# mcu.net
KiCad netlist of a schematic drawn in Altium Designer
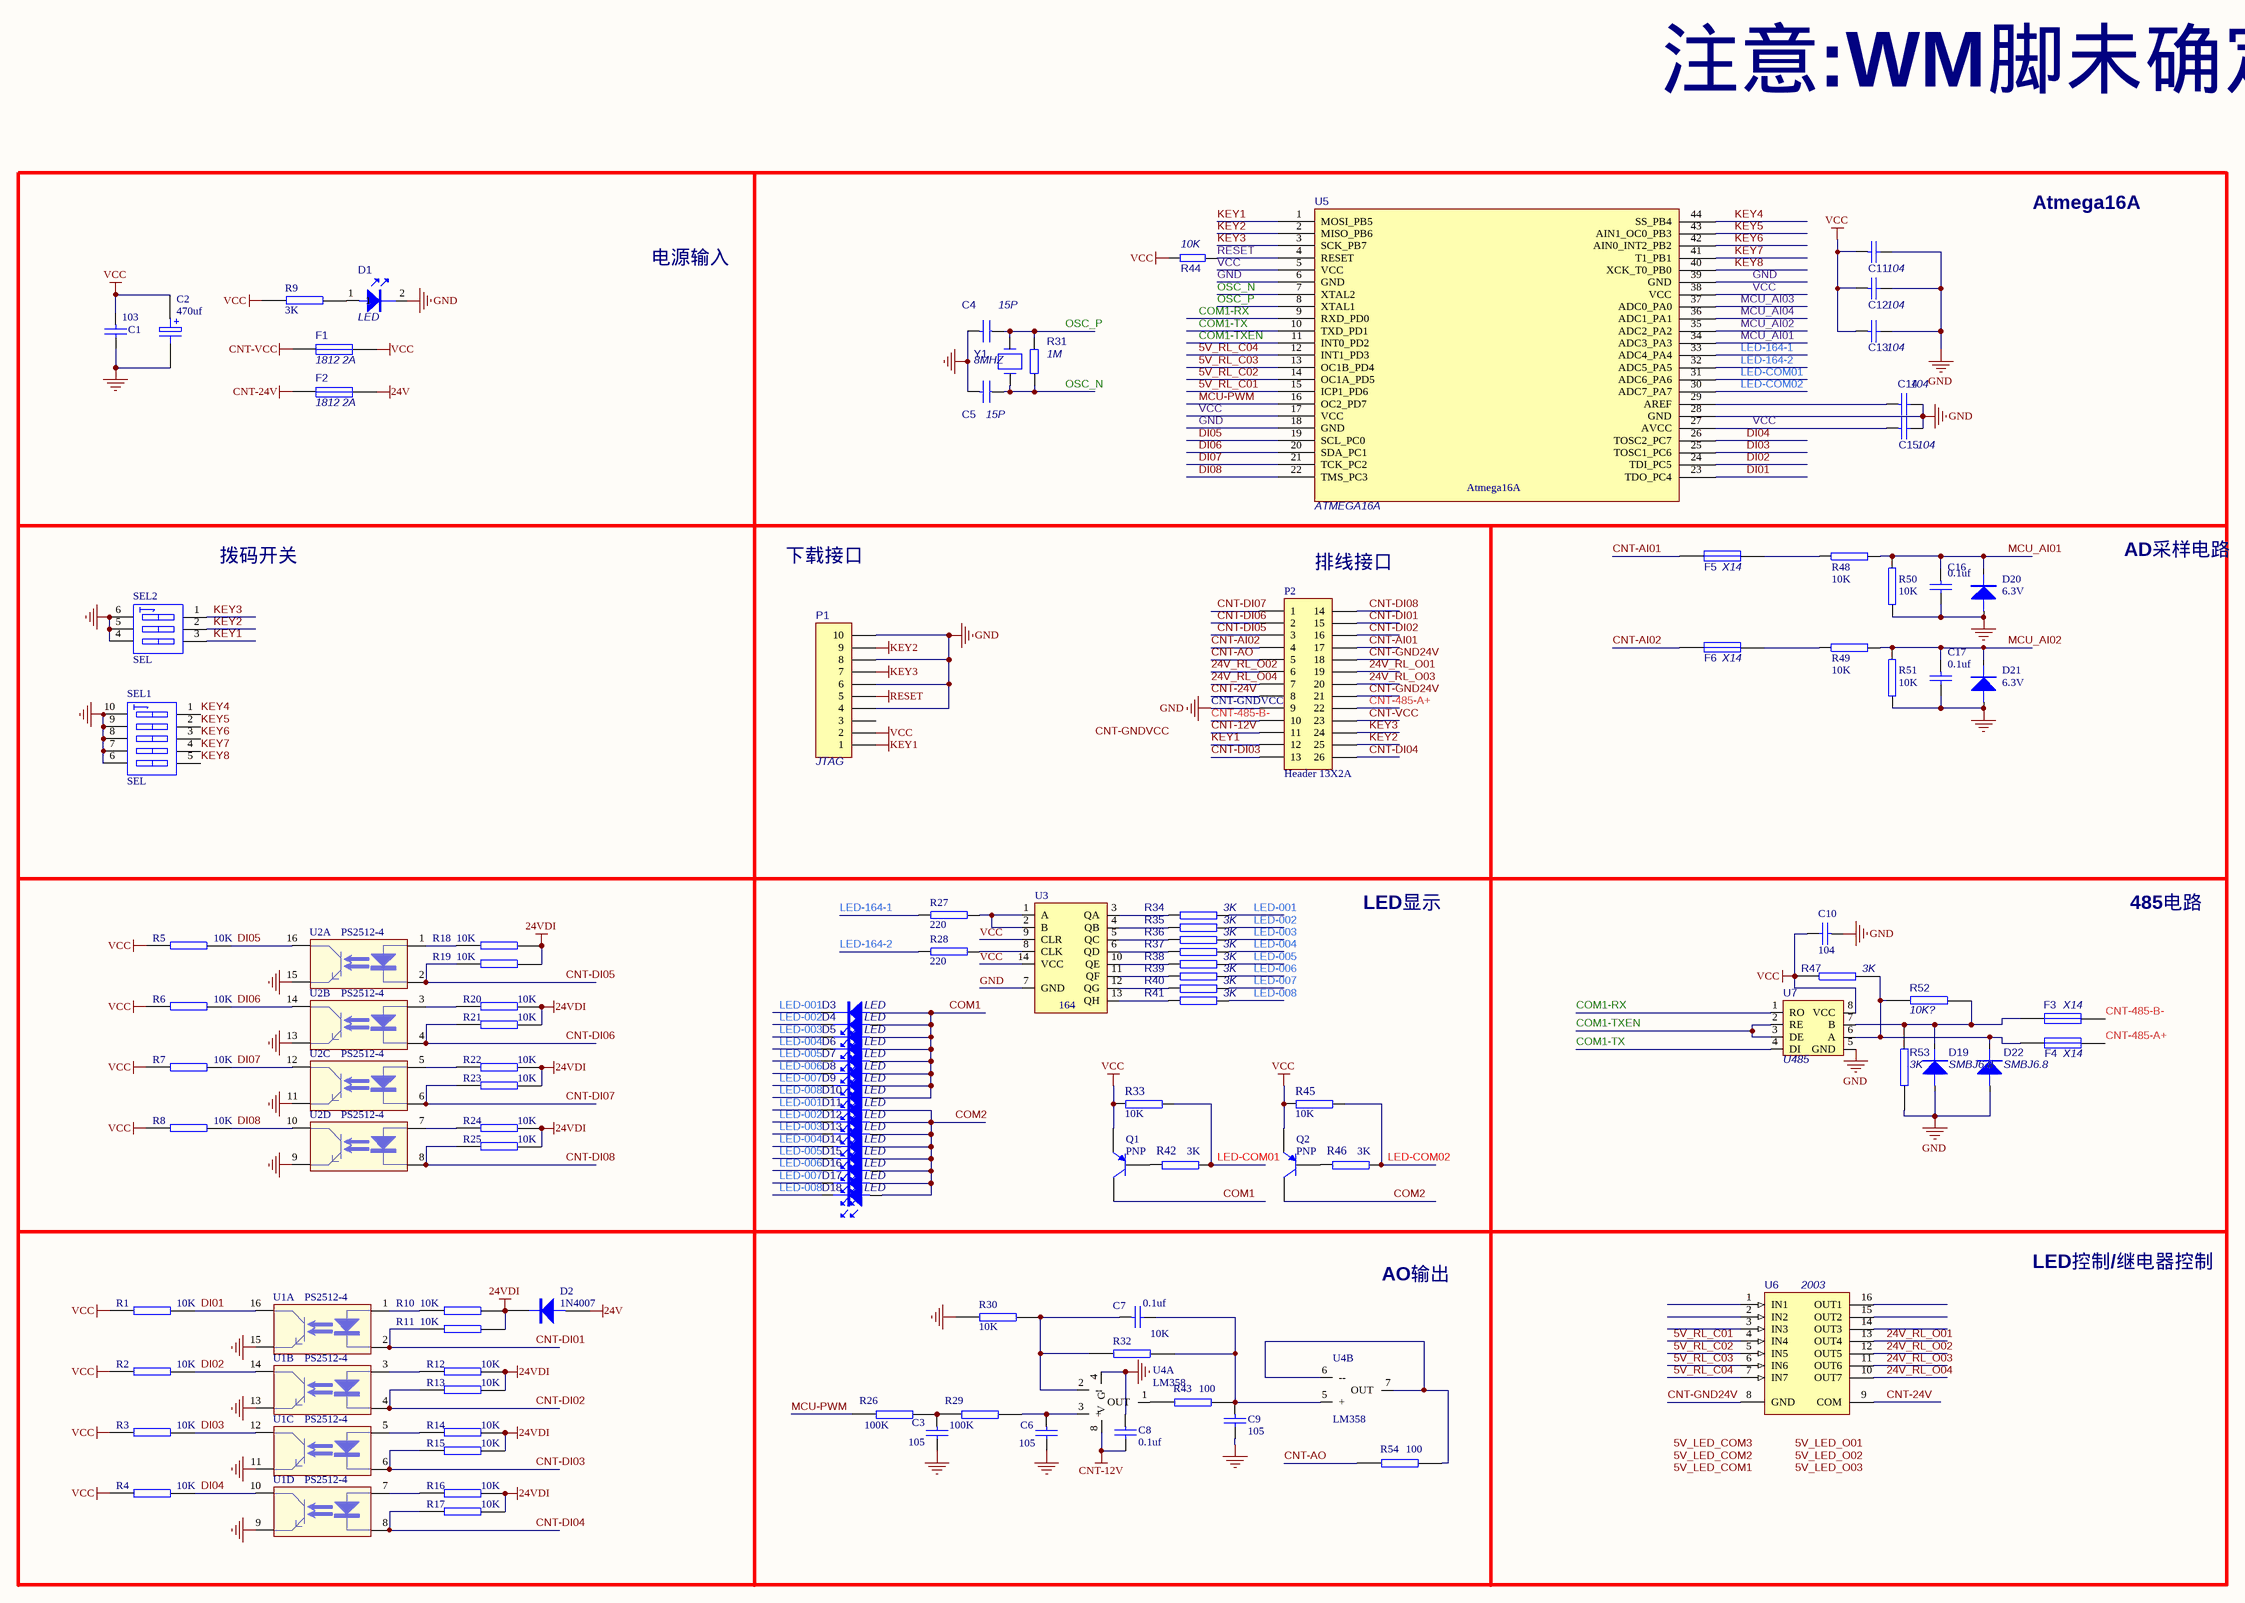
[diagram p0: mcu.SchDoc]

(export (version "E")
  (design (tool "Eeschema 10.0.6"))
  (components
    (comp (ref "C1")
      (value "103")
      (footprint "C0805")
      (description "Capacitor")
      (libsource (lib "*") (part "CAP"))
    )
    (comp (ref "C2")
      (value "470uf")
      (footprint "E8MM")
      (description "Electrolytic Capacitor")
      (libsource (lib "*") (part "ELECTRO1"))
    )
    (comp (ref "C3")
      (value "105")
      (footprint "c0805")
      (description "Capacitor")
      (libsource (lib "*") (part "CAP"))
    )
    (comp (ref "C4") (value "15P") (footprint "C0805") (libsource (lib "*") (part "CAP NP")))
    (comp (ref "C5") (value "15P") (footprint "C0805") (libsource (lib "*") (part "CAP NP")))
    (comp (ref "C6")
      (value "105")
      (footprint "c0805")
      (description "Capacitor")
      (libsource (lib "*") (part "CAP"))
    )
    (comp (ref "C7")
      (value "0.1uf")
      (footprint "C0805")
      (description "Capacitor")
      (libsource (lib "*") (part "CAP"))
    )
    (comp (ref "C8")
      (value "0.1uf")
      (footprint "C0805")
      (description "Capacitor")
      (libsource (lib "*") (part "CAP"))
    )
    (comp (ref "C9")
      (value "105")
      (footprint "c0805")
      (description "Capacitor")
      (libsource (lib "*") (part "CAP"))
    )
    (comp (ref "C10")
      (value "104")
      (footprint "C0805")
      (description "Capacitor")
      (libsource (lib "*") (part "CAP"))
    )
    (comp (ref "C11")
      (value "104")
      (footprint "C0805")
      (description "Capacitor")
      (libsource (lib "*") (part "CAP"))
    )
    (comp (ref "C12")
      (value "104")
      (footprint "C0805")
      (description "Capacitor")
      (libsource (lib "*") (part "CAP"))
    )
    (comp (ref "C13")
      (value "104")
      (footprint "C0805")
      (description "Capacitor")
      (libsource (lib "*") (part "CAP"))
    )
    (comp (ref "C14")
      (value "104")
      (footprint "C0805")
      (description "Capacitor")
      (libsource (lib "*") (part "CAP"))
    )
    (comp (ref "C15")
      (value "104")
      (footprint "C0805")
      (description "Capacitor")
      (libsource (lib "*") (part "CAP"))
    )
    (comp (ref "C16")
      (value "0.1uf")
      (footprint "C0805")
      (description "Capacitor")
      (libsource (lib "*") (part "CAP"))
    )
    (comp (ref "C17")
      (value "0.1uf")
      (footprint "C0805")
      (description "Capacitor")
      (libsource (lib "*") (part "CAP"))
    )
    (comp (ref "D1") (value "LED") (footprint "LED0805") (libsource (lib "*") (part "LED")))
    (comp (ref "D2")
      (value "1N4007")
      (footprint "M7")
      (description "Diode")
      (libsource (lib "") (part "DIODE_1"))
    )
    (comp (ref "D3") (value "LED") (footprint "LED0805") (libsource (lib "") (part "LED_1")))
    (comp (ref "D4") (value "LED") (footprint "LED0805") (libsource (lib "") (part "LED_1")))
    (comp (ref "D5") (value "LED") (footprint "LED0805") (libsource (lib "") (part "LED_1")))
    (comp (ref "D6") (value "LED") (footprint "LED0805") (libsource (lib "") (part "LED_1")))
    (comp (ref "D7") (value "LED") (footprint "LED0805") (libsource (lib "") (part "LED_1")))
    (comp (ref "D8") (value "LED") (footprint "LED0805") (libsource (lib "") (part "LED_1")))
    (comp (ref "D9") (value "LED") (footprint "LED0805") (libsource (lib "") (part "LED_1")))
    (comp (ref "D10") (value "LED") (footprint "LED0805") (libsource (lib "") (part "LED_1")))
    (comp (ref "D11") (value "LED") (footprint "LED0805") (libsource (lib "") (part "LED_1")))
    (comp (ref "D12") (value "LED") (footprint "LED0805") (libsource (lib "") (part "LED_1")))
    (comp (ref "D13") (value "LED") (footprint "LED0805") (libsource (lib "") (part "LED_1")))
    (comp (ref "D14") (value "LED") (footprint "LED0805") (libsource (lib "") (part "LED_1")))
    (comp (ref "D15") (value "LED") (footprint "LED0805") (libsource (lib "") (part "LED_1")))
    (comp (ref "D16") (value "LED") (footprint "LED0805") (libsource (lib "") (part "LED_1")))
    (comp (ref "D17") (value "LED") (footprint "LED0805") (libsource (lib "") (part "LED_1")))
    (comp (ref "D18") (value "LED") (footprint "LED0805") (libsource (lib "") (part "LED_1")))
    (comp (ref "D19")
      (value "SMBJ6.8")
      (footprint "SMBJ_SMT")
      (description "Diode")
      (libsource (lib "*") (part "DIODE"))
    )
    (comp (ref "D20")
      (value "6.3V")
      (footprint "1206AK")
      (description "Diode")
      (libsource (lib "*") (part "DIODE"))
    )
    (comp (ref "D21")
      (value "6.3V")
      (footprint "1206AK")
      (description "Diode")
      (libsource (lib "*") (part "DIODE"))
    )
    (comp (ref "D22")
      (value "SMBJ6.8")
      (footprint "SMBJ_SMT")
      (description "Diode")
      (libsource (lib "*") (part "DIODE"))
    )
    (comp (ref "F1")
      (value "1812 2A")
      (footprint "F1210")
      (description "Fuse")
      (fields (field (name "PUBLISHER") "Altium Limited"))
      (libsource (lib "Miscellaneous Devices") (part "Fuse 1"))
    )
    (comp (ref "F2")
      (value "1812 2A")
      (footprint "F1210")
      (description "Fuse")
      (fields (field (name "PUBLISHER") "Altium Limited"))
      (libsource (lib "Miscellaneous Devices") (part "Fuse 1"))
    )
    (comp (ref "F3")
      (value "X14")
      (footprint "F1210")
      (description "Fuse")
      (fields (field (name "PUBLISHER") "Altium Limited"))
      (libsource (lib "Miscellaneous Devices") (part "Fuse 1"))
    )
    (comp (ref "F4")
      (value "X14")
      (footprint "F1210")
      (description "Fuse")
      (fields (field (name "PUBLISHER") "Altium Limited"))
      (libsource (lib "Miscellaneous Devices") (part "Fuse 1"))
    )
    (comp (ref "F5")
      (value "X14")
      (footprint "F1210")
      (description "Fuse")
      (fields (field (name "PUBLISHER") "Altium Limited"))
      (libsource (lib "Miscellaneous Devices") (part "Fuse 1"))
    )
    (comp (ref "F6")
      (value "X14")
      (footprint "F1210")
      (description "Fuse")
      (fields (field (name "PUBLISHER") "Altium Limited"))
      (libsource (lib "Miscellaneous Devices") (part "Fuse 1"))
    )
    (comp (ref "P1")
      (value "JTAG")
      (footprint "FC10")
      (description "Connector")
      (libsource (lib "*") (part "CON10"))
    )
    (comp (ref "P2")
      (value "Header 13X2A")
      (footprint "HDR2X13_CEN")
      (description "Header, 13-Pin, Dual row")
      (fields (field (name "PUBLISHER") "Altium Limited"))
      (libsource (lib "Miscellaneous Connectors") (part "Header 13X2A"))
    )
    (comp (ref "Q1")
      (value "PNP")
      (footprint "SOT23")
      (description "PNP Bipolar Transistor")
      (fields (field (name "PUBLISHER") "Altium Limited"))
      (libsource (lib "Miscellaneous Devices") (part "PNP"))
    )
    (comp (ref "Q2")
      (value "PNP")
      (footprint "SOT23")
      (description "PNP Bipolar Transistor")
      (fields (field (name "PUBLISHER") "Altium Limited"))
      (libsource (lib "Miscellaneous Devices") (part "PNP"))
    )
    (comp (ref "R1") (value "10K") (footprint "0805R") (libsource (lib "*") (part "RES2")))
    (comp (ref "R2") (value "10K") (footprint "0805R") (libsource (lib "*") (part "RES2")))
    (comp (ref "R3") (value "10K") (footprint "0805R") (libsource (lib "*") (part "RES2")))
    (comp (ref "R4") (value "10K") (footprint "0805R") (libsource (lib "*") (part "RES2")))
    (comp (ref "R5") (value "10K") (footprint "0805R") (libsource (lib "*") (part "RES2")))
    (comp (ref "R6") (value "10K") (footprint "0805R") (libsource (lib "*") (part "RES2")))
    (comp (ref "R7") (value "10K") (footprint "0805R") (libsource (lib "*") (part "RES2")))
    (comp (ref "R8") (value "10K") (footprint "0805R") (libsource (lib "*") (part "RES2")))
    (comp (ref "R9") (value "3K") (footprint "0805R") (libsource (lib "*") (part "RES2")))
    (comp (ref "R10") (value "10K") (footprint "0805R") (libsource (lib "*") (part "RES2")))
    (comp (ref "R11") (value "10K") (footprint "0805R") (libsource (lib "*") (part "RES2")))
    (comp (ref "R12") (value "10K") (footprint "0805R") (libsource (lib "*") (part "RES2")))
    (comp (ref "R13") (value "10K") (footprint "0805R") (libsource (lib "*") (part "RES2")))
    (comp (ref "R14") (value "10K") (footprint "0805R") (libsource (lib "*") (part "RES2")))
    (comp (ref "R15") (value "10K") (footprint "0805R") (libsource (lib "*") (part "RES2")))
    (comp (ref "R16") (value "10K") (footprint "0805R") (libsource (lib "*") (part "RES2")))
    (comp (ref "R17") (value "10K") (footprint "0805R") (libsource (lib "*") (part "RES2")))
    (comp (ref "R18") (value "10K") (footprint "0805R") (libsource (lib "*") (part "RES2")))
    (comp (ref "R19") (value "10K") (footprint "0805R") (libsource (lib "*") (part "RES2")))
    (comp (ref "R20") (value "10K") (footprint "0805R") (libsource (lib "*") (part "RES2")))
    (comp (ref "R21") (value "10K") (footprint "0805R") (libsource (lib "*") (part "RES2")))
    (comp (ref "R22") (value "10K") (footprint "0805R") (libsource (lib "*") (part "RES2")))
    (comp (ref "R23") (value "10K") (footprint "0805R") (libsource (lib "*") (part "RES2")))
    (comp (ref "R24") (value "10K") (footprint "0805R") (libsource (lib "*") (part "RES2")))
    (comp (ref "R25") (value "10K") (footprint "0805R") (libsource (lib "*") (part "RES2")))
    (comp (ref "R26") (value "100K") (footprint "0805R") (libsource (lib "*") (part "RES2")))
    (comp (ref "R27") (value "220") (footprint "0805R") (libsource (lib "") (part "RES2_3")))
    (comp (ref "R28") (value "220") (footprint "0805R") (libsource (lib "") (part "RES2_3")))
    (comp (ref "R29") (value "100K") (footprint "0805R") (libsource (lib "*") (part "RES2")))
    (comp (ref "R30") (value "10K") (footprint "0805R") (libsource (lib "*") (part "RES2")))
    (comp (ref "R31") (value "1M") (footprint "0805R") (libsource (lib "*") (part "res")))
    (comp (ref "R32") (value "10K") (footprint "0805R") (libsource (lib "*") (part "RES2")))
    (comp (ref "R33") (value "10K") (footprint "0805R") (libsource (lib "") (part "RES2_2")))
    (comp (ref "R34") (value "3K") (footprint "0805R") (libsource (lib "") (part "RES2_1")))
    (comp (ref "R35") (value "3K") (footprint "0805R") (libsource (lib "") (part "RES2_1")))
    (comp (ref "R36") (value "3K") (footprint "0805R") (libsource (lib "") (part "RES2_1")))
    (comp (ref "R37") (value "3K") (footprint "0805R") (libsource (lib "") (part "RES2_1")))
    (comp (ref "R38") (value "3K") (footprint "0805R") (libsource (lib "") (part "RES2_1")))
    (comp (ref "R39") (value "3K") (footprint "0805R") (libsource (lib "") (part "RES2_1")))
    (comp (ref "R40") (value "3K") (footprint "0805R") (libsource (lib "") (part "RES2_1")))
    (comp (ref "R41") (value "3K") (footprint "0805R") (libsource (lib "") (part "RES2_1")))
    (comp (ref "R42") (value "3K") (footprint "0805R") (libsource (lib "") (part "RES2_2")))
    (comp (ref "R43") (value "100") (footprint "0805R") (libsource (lib "*") (part "RES2")))
    (comp (ref "R44") (value "10K") (footprint "0805R") (libsource (lib "*") (part "res")))
    (comp (ref "R45") (value "10K") (footprint "0805R") (libsource (lib "") (part "RES2_2")))
    (comp (ref "R46") (value "3K") (footprint "0805R") (libsource (lib "") (part "RES2_2")))
    (comp (ref "R47") (value "3K") (footprint "0805R") (libsource (lib "*") (part "RES2")))
    (comp (ref "R48") (value "10K") (footprint "0805R") (libsource (lib "") (part "RES2_1")))
    (comp (ref "R49") (value "10K") (footprint "0805R") (libsource (lib "") (part "RES2_1")))
    (comp (ref "R50") (value "10K") (footprint "0805R") (libsource (lib "") (part "RES2_1")))
    (comp (ref "R51") (value "10K") (footprint "0805R") (libsource (lib "") (part "RES2_1")))
    (comp (ref "R52") (value "10K?") (footprint "0805R") (libsource (lib "*") (part "RES2")))
    (comp (ref "R53") (value "3K") (footprint "0805R") (libsource (lib "*") (part "RES2")))
    (comp (ref "R54") (value "100") (footprint "0805R") (libsource (lib "*") (part "RES2")))
    (comp (ref "SEL1")
      (value "SEL")
      (footprint "N10A")
      (description "DIP Switch, 5 Position, SPST")
      (fields (field (name "PUBLISHER") "Altium Limited"))
      (libsource (lib "Miscellaneous Devices") (part "SW DIP-5"))
    )
    (comp (ref "SEL2")
      (value "SEL")
      (footprint "DIP-6")
      (description "DIP Switch, 3 Position, SPST")
      (fields (field (name "PUBLISHER") "Altium Limited"))
      (libsource (lib "Miscellaneous Devices") (part "SW DIP-3"))
    )
    (comp (ref "U1") (value "PS2512-4") (footprint "SO_16") (libsource (lib "Atkey_2") (part "PS2512-4")))
    (comp (ref "U2") (value "PS2512-4") (footprint "SO_16") (libsource (lib "Atkey_2") (part "PS2512-4")))
    (comp (ref "U3") (value "164") (footprint "SO_14") (libsource (lib "*") (part "164")))
    (comp (ref "U4") (value "LM358") (footprint "SO_08") (libsource (lib "*") (part "LM358")))
    (comp (ref "U5") (value "ATMEGA16A") (footprint "qfp44") (libsource (lib "CL-FFU") (part "ATMEGA16A")))
    (comp (ref "U6")
      (value "2003")
      (footprint "SO_16")
      (description "High-Voltage, High-Current Darlington Array")
      (fields (field (name "PUBLISHER") "*"))
      (libsource (lib "*") (part "ULN2003A"))
    )
    (comp (ref "U7") (value "U485") (footprint "SOP8") (libsource (lib "POL485") (part "U485")))
    (comp (ref "Y1") (value "8MHZ") (footprint "XAL2") (libsource (lib "*") (part "CRYSTAL")))
  )
  (nets
    (net (code "7") (name "/5V_RL_C01") (class "Default")
      (node (ref "U5") (pin "15") (pinfunction "ICP1_PD6_15") (pintype "passive"))
      (node (ref "U6") (pin "4") (pinfunction "IN4_4") (pintype "input"))
    )
    (net (code "8") (name "/5V_RL_C02") (class "Default")
      (node (ref "U5") (pin "14") (pinfunction "OC1A_PD5_14") (pintype "passive"))
      (node (ref "U6") (pin "5") (pinfunction "IN5_5") (pintype "input"))
    )
    (net (code "9") (name "/5V_RL_C03") (class "Default")
      (node (ref "U5") (pin "13") (pinfunction "OC1B_PD4_13") (pintype "passive"))
      (node (ref "U6") (pin "6") (pinfunction "IN6_6") (pintype "input"))
    )
    (net (code "10") (name "/5V_RL_C04") (class "Default")
      (node (ref "U5") (pin "12") (pinfunction "INT1_PD3_12") (pintype "passive"))
      (node (ref "U6") (pin "7") (pinfunction "IN7_7") (pintype "input"))
    )
    (net (code "11") (name "/24V_RL_O01") (class "Default")
      (node (ref "P2") (pin "19") (pinfunction "19_19") (pintype "passive"))
      (node (ref "U6") (pin "13") (pinfunction "OUT4_13") (pintype "open_collector"))
    )
    (net (code "12") (name "/24V_RL_O02") (class "Default")
      (node (ref "P2") (pin "6") (pinfunction "6_6") (pintype "passive"))
      (node (ref "U6") (pin "12") (pinfunction "OUT5_12") (pintype "open_collector"))
    )
    (net (code "13") (name "/24V_RL_O03") (class "Default")
      (node (ref "P2") (pin "20") (pinfunction "20_20") (pintype "passive"))
      (node (ref "U6") (pin "11") (pinfunction "OUT6_11") (pintype "open_collector"))
    )
    (net (code "14") (name "/24V_RL_O04") (class "Default")
      (node (ref "P2") (pin "7") (pinfunction "7_7") (pintype "passive"))
      (node (ref "U6") (pin "10") (pinfunction "OUT7_10") (pintype "open_collector"))
    )
    (net (code "15") (name "/CNT-485-A+") (class "Default")
      (node (ref "F4") (pin "1") (pinfunction "1_1") (pintype "passive"))
      (node (ref "P2") (pin "22") (pinfunction "22_22") (pintype "passive"))
    )
    (net (code "16") (name "/CNT-485-B-") (class "Default")
      (node (ref "F3") (pin "1") (pinfunction "1_1") (pintype "passive"))
      (node (ref "P2") (pin "10") (pinfunction "10_10") (pintype "passive"))
    )
    (net (code "17") (name "/CNT-AI01") (class "Default")
      (node (ref "F5") (pin "2") (pinfunction "2_2") (pintype "passive"))
      (node (ref "P2") (pin "17") (pinfunction "17_17") (pintype "passive"))
    )
    (net (code "18") (name "/CNT-AI02") (class "Default")
      (node (ref "F6") (pin "2") (pinfunction "2_2") (pintype "passive"))
      (node (ref "P2") (pin "4") (pinfunction "4_4") (pintype "passive"))
    )
    (net (code "19") (name "/CNT-AO") (class "Default")
      (node (ref "P2") (pin "5") (pinfunction "5_5") (pintype "passive"))
      (node (ref "R54") (pin "1") (pinfunction "1_1") (pintype "passive"))
    )
    (net (code "20") (name "/CNT-DI01") (class "Default")
      (node (ref "P2") (pin "15") (pinfunction "15_15") (pintype "passive"))
      (node (ref "R11") (pin "2") (pinfunction "2_2") (pintype "passive"))
      (node (ref "U1") (pin "2") (pinfunction "2_2") (pintype "passive"))
    )
    (net (code "21") (name "/CNT-DI02") (class "Default")
      (node (ref "P2") (pin "16") (pinfunction "16_16") (pintype "passive"))
      (node (ref "R13") (pin "2") (pinfunction "2_2") (pintype "passive"))
      (node (ref "U1") (pin "4") (pinfunction "4_4") (pintype "passive"))
    )
    (net (code "22") (name "/CNT-DI03") (class "Default")
      (node (ref "P2") (pin "13") (pinfunction "13_13") (pintype "passive"))
      (node (ref "R15") (pin "2") (pinfunction "2_2") (pintype "passive"))
      (node (ref "U1") (pin "6") (pinfunction "6_6") (pintype "passive"))
    )
    (net (code "23") (name "/CNT-DI04") (class "Default")
      (node (ref "P2") (pin "26") (pinfunction "26_26") (pintype "passive"))
      (node (ref "R17") (pin "2") (pinfunction "2_2") (pintype "passive"))
      (node (ref "U1") (pin "8") (pinfunction "8_8") (pintype "passive"))
    )
    (net (code "24") (name "/CNT-DI05") (class "Default")
      (node (ref "P2") (pin "3") (pinfunction "3_3") (pintype "passive"))
      (node (ref "R19") (pin "2") (pinfunction "2_2") (pintype "passive"))
      (node (ref "U2") (pin "2") (pinfunction "2_2") (pintype "passive"))
    )
    (net (code "25") (name "/CNT-DI06") (class "Default")
      (node (ref "P2") (pin "2") (pinfunction "2_2") (pintype "passive"))
      (node (ref "R21") (pin "2") (pinfunction "2_2") (pintype "passive"))
      (node (ref "U2") (pin "4") (pinfunction "4_4") (pintype "passive"))
    )
    (net (code "26") (name "/CNT-DI07") (class "Default")
      (node (ref "P2") (pin "1") (pinfunction "1_1") (pintype "passive"))
      (node (ref "R23") (pin "2") (pinfunction "2_2") (pintype "passive"))
      (node (ref "U2") (pin "6") (pinfunction "6_6") (pintype "passive"))
    )
    (net (code "27") (name "/CNT-DI08") (class "Default")
      (node (ref "P2") (pin "14") (pinfunction "14_14") (pintype "passive"))
      (node (ref "R25") (pin "2") (pinfunction "2_2") (pintype "passive"))
      (node (ref "U2") (pin "8") (pinfunction "8_8") (pintype "passive"))
    )
    (net (code "28") (name "/CNT-GND24V") (class "Default")
      (node (ref "P2") (pin "18") (pinfunction "18_18") (pintype "passive"))
      (node (ref "P2") (pin "21") (pinfunction "21_21") (pintype "passive"))
      (node (ref "U6") (pin "8") (pinfunction "GND_8") (pintype "power_in"))
    )
    (net (code "30") (name "/COM1") (class "Default")
      (node (ref "D10") (pin "1") (pinfunction "1_1") (pintype "passive"))
      (node (ref "D3") (pin "1") (pinfunction "1_1") (pintype "passive"))
      (node (ref "D4") (pin "1") (pinfunction "1_1") (pintype "passive"))
      (node (ref "D5") (pin "1") (pinfunction "1_1") (pintype "passive"))
      (node (ref "D6") (pin "1") (pinfunction "1_1") (pintype "passive"))
      (node (ref "D7") (pin "1") (pinfunction "1_1") (pintype "passive"))
      (node (ref "D8") (pin "1") (pinfunction "1_1") (pintype "passive"))
      (node (ref "D9") (pin "1") (pinfunction "1_1") (pintype "passive"))
      (node (ref "Q1") (pin "1") (pinfunction "C_1") (pintype "passive"))
    )
    (net (code "31") (name "/COM1-RX") (class "Default")
      (node (ref "U5") (pin "9") (pinfunction "RXD_PD0_9") (pintype "passive"))
      (node (ref "U7") (pin "1") (pinfunction "RO_1") (pintype "passive"))
    )
    (net (code "32") (name "/COM1-TX") (class "Default")
      (node (ref "U5") (pin "10") (pinfunction "TXD_PD1_10") (pintype "passive"))
      (node (ref "U7") (pin "4") (pinfunction "DI_4") (pintype "passive"))
    )
    (net (code "33") (name "/COM1-TXEN") (class "Default")
      (node (ref "U5") (pin "11") (pinfunction "INT0_PD2_11") (pintype "passive"))
      (node (ref "U7") (pin "2") (pinfunction "RE_2") (pintype "passive"))
      (node (ref "U7") (pin "3") (pinfunction "DE_3") (pintype "passive"))
    )
    (net (code "34") (name "/COM2") (class "Default")
      (node (ref "D11") (pin "1") (pinfunction "1_1") (pintype "passive"))
      (node (ref "D12") (pin "1") (pinfunction "1_1") (pintype "passive"))
      (node (ref "D13") (pin "1") (pinfunction "1_1") (pintype "passive"))
      (node (ref "D14") (pin "1") (pinfunction "1_1") (pintype "passive"))
      (node (ref "D15") (pin "1") (pinfunction "1_1") (pintype "passive"))
      (node (ref "D16") (pin "1") (pinfunction "1_1") (pintype "passive"))
      (node (ref "D17") (pin "1") (pinfunction "1_1") (pintype "passive"))
      (node (ref "D18") (pin "1") (pinfunction "1_1") (pintype "passive"))
      (node (ref "Q2") (pin "1") (pinfunction "C_1") (pintype "passive"))
    )
    (net (code "35") (name "/DI01") (class "Default")
      (node (ref "R1") (pin "1") (pinfunction "1_1") (pintype "passive"))
      (node (ref "U1") (pin "16") (pinfunction "16_16") (pintype "passive"))
      (node (ref "U5") (pin "23") (pinfunction "TDO_PC4_23") (pintype "passive"))
    )
    (net (code "36") (name "/DI02") (class "Default")
      (node (ref "R2") (pin "1") (pinfunction "1_1") (pintype "passive"))
      (node (ref "U1") (pin "14") (pinfunction "14_14") (pintype "passive"))
      (node (ref "U5") (pin "24") (pinfunction "TDI_PC5_24") (pintype "passive"))
    )
    (net (code "37") (name "/DI03") (class "Default")
      (node (ref "R3") (pin "1") (pinfunction "1_1") (pintype "passive"))
      (node (ref "U1") (pin "12") (pinfunction "12_12") (pintype "passive"))
      (node (ref "U5") (pin "25") (pinfunction "TOSC1_PC6_25") (pintype "passive"))
    )
    (net (code "38") (name "/DI04") (class "Default")
      (node (ref "R4") (pin "1") (pinfunction "1_1") (pintype "passive"))
      (node (ref "U1") (pin "10") (pinfunction "10_10") (pintype "passive"))
      (node (ref "U5") (pin "26") (pinfunction "TOSC2_PC7_26") (pintype "passive"))
    )
    (net (code "39") (name "/DI05") (class "Default")
      (node (ref "R5") (pin "1") (pinfunction "1_1") (pintype "passive"))
      (node (ref "U2") (pin "16") (pinfunction "16_16") (pintype "passive"))
      (node (ref "U5") (pin "19") (pinfunction "SCL_PC0_19") (pintype "passive"))
    )
    (net (code "40") (name "/DI06") (class "Default")
      (node (ref "R6") (pin "1") (pinfunction "1_1") (pintype "passive"))
      (node (ref "U2") (pin "14") (pinfunction "14_14") (pintype "passive"))
      (node (ref "U5") (pin "20") (pinfunction "SDA_PC1_20") (pintype "passive"))
    )
    (net (code "41") (name "/DI07") (class "Default")
      (node (ref "R7") (pin "1") (pinfunction "1_1") (pintype "passive"))
      (node (ref "U2") (pin "12") (pinfunction "12_12") (pintype "passive"))
      (node (ref "U5") (pin "21") (pinfunction "TCK_PC2_21") (pintype "passive"))
    )
    (net (code "42") (name "/DI08") (class "Default")
      (node (ref "R8") (pin "1") (pinfunction "1_1") (pintype "passive"))
      (node (ref "U2") (pin "10") (pinfunction "10_10") (pintype "passive"))
      (node (ref "U5") (pin "22") (pinfunction "TMS_PC3_22") (pintype "passive"))
    )
    (net (code "43") (name "/KEY4") (class "Default")
      (node (ref "SEL1") (pin "1") (pinfunction "A1_1") (pintype "passive"))
      (node (ref "U5") (pin "44") (pinfunction "SS_PB4_44") (pintype "passive"))
    )
    (net (code "44") (name "/KEY5") (class "Default")
      (node (ref "SEL1") (pin "2") (pinfunction "A2_2") (pintype "passive"))
      (node (ref "U5") (pin "43") (pinfunction "AIN1_OC0_PB3_43") (pintype "passive"))
    )
    (net (code "45") (name "/KEY6") (class "Default")
      (node (ref "SEL1") (pin "3") (pinfunction "A3_3") (pintype "passive"))
      (node (ref "U5") (pin "42") (pinfunction "AIN0_INT2_PB2_42") (pintype "passive"))
    )
    (net (code "46") (name "/KEY7") (class "Default")
      (node (ref "SEL1") (pin "4") (pinfunction "A4_4") (pintype "passive"))
      (node (ref "U5") (pin "41") (pinfunction "T1_PB1_41") (pintype "passive"))
    )
    (net (code "47") (name "/KEY8") (class "Default")
      (node (ref "SEL1") (pin "5") (pinfunction "A5_5") (pintype "passive"))
      (node (ref "U5") (pin "40") (pinfunction "XCK_T0_PB0_40") (pintype "passive"))
    )
    (net (code "48") (name "/LED-001") (class "Default")
      (node (ref "D11") (pin "2") (pinfunction "2_2") (pintype "passive"))
      (node (ref "D3") (pin "2") (pinfunction "2_2") (pintype "passive"))
      (node (ref "R34") (pin "2") (pinfunction "2_2") (pintype "passive"))
    )
    (net (code "49") (name "/LED-002") (class "Default")
      (node (ref "D12") (pin "2") (pinfunction "2_2") (pintype "passive"))
      (node (ref "D4") (pin "2") (pinfunction "2_2") (pintype "passive"))
      (node (ref "R35") (pin "2") (pinfunction "2_2") (pintype "passive"))
    )
    (net (code "50") (name "/LED-003") (class "Default")
      (node (ref "D13") (pin "2") (pinfunction "2_2") (pintype "passive"))
      (node (ref "D5") (pin "2") (pinfunction "2_2") (pintype "passive"))
      (node (ref "R36") (pin "2") (pinfunction "2_2") (pintype "passive"))
    )
    (net (code "51") (name "/LED-004") (class "Default")
      (node (ref "D14") (pin "2") (pinfunction "2_2") (pintype "passive"))
      (node (ref "D6") (pin "2") (pinfunction "2_2") (pintype "passive"))
      (node (ref "R37") (pin "2") (pinfunction "2_2") (pintype "passive"))
    )
    (net (code "52") (name "/LED-005") (class "Default")
      (node (ref "D15") (pin "2") (pinfunction "2_2") (pintype "passive"))
      (node (ref "D7") (pin "2") (pinfunction "2_2") (pintype "passive"))
      (node (ref "R38") (pin "2") (pinfunction "2_2") (pintype "passive"))
    )
    (net (code "53") (name "/LED-006") (class "Default")
      (node (ref "D16") (pin "2") (pinfunction "2_2") (pintype "passive"))
      (node (ref "D8") (pin "2") (pinfunction "2_2") (pintype "passive"))
      (node (ref "R39") (pin "2") (pinfunction "2_2") (pintype "passive"))
    )
    (net (code "54") (name "/LED-007") (class "Default")
      (node (ref "D17") (pin "2") (pinfunction "2_2") (pintype "passive"))
      (node (ref "D9") (pin "2") (pinfunction "2_2") (pintype "passive"))
      (node (ref "R40") (pin "2") (pinfunction "2_2") (pintype "passive"))
    )
    (net (code "55") (name "/LED-008") (class "Default")
      (node (ref "D10") (pin "2") (pinfunction "2_2") (pintype "passive"))
      (node (ref "D18") (pin "2") (pinfunction "2_2") (pintype "passive"))
      (node (ref "R41") (pin "2") (pinfunction "2_2") (pintype "passive"))
    )
    (net (code "56") (name "/LED-164-1") (class "Default")
      (node (ref "R27") (pin "2") (pinfunction "2_2") (pintype "passive"))
      (node (ref "U5") (pin "33") (pinfunction "ADC4_PA4_33") (pintype "passive"))
    )
    (net (code "57") (name "/LED-164-2") (class "Default")
      (node (ref "R28") (pin "2") (pinfunction "2_2") (pintype "passive"))
      (node (ref "U5") (pin "32") (pinfunction "ADC5_PA5_32") (pintype "passive"))
    )
    (net (code "58") (name "/LED-COM01") (class "Default")
      (node (ref "R33") (pin "2") (pintype "passive"))
      (node (ref "R42") (pin "2") (pintype "passive"))
      (node (ref "U5") (pin "31") (pinfunction "ADC6_PA6_31") (pintype "passive"))
    )
    (net (code "59") (name "/LED-COM02") (class "Default")
      (node (ref "R45") (pin "2") (pintype "passive"))
      (node (ref "R46") (pin "2") (pintype "passive"))
      (node (ref "U5") (pin "30") (pinfunction "ADC7_PA7_30") (pintype "passive"))
    )
    (net (code "60") (name "/MCU-PWM") (class "Default")
      (node (ref "R26") (pin "1") (pinfunction "1_1") (pintype "passive"))
      (node (ref "U5") (pin "16") (pinfunction "OC2_PD7_16") (pintype "passive"))
    )
    (net (code "61") (name "/MCU_AI01") (class "Default")
      (node (ref "C16") (pin "1") (pinfunction "1_1") (pintype "passive"))
      (node (ref "D20") (pin "K") (pinfunction "K_K") (pintype "passive"))
      (node (ref "R48") (pin "2") (pinfunction "2_2") (pintype "passive"))
      (node (ref "R50") (pin "2") (pinfunction "2_2") (pintype "passive"))
      (node (ref "U5") (pin "34") (pinfunction "ADC3_PA3_34") (pintype "passive"))
    )
    (net (code "62") (name "/MCU_AI02") (class "Default")
      (node (ref "C17") (pin "1") (pinfunction "1_1") (pintype "passive"))
      (node (ref "D21") (pin "K") (pinfunction "K_K") (pintype "passive"))
      (node (ref "R49") (pin "2") (pinfunction "2_2") (pintype "passive"))
      (node (ref "R51") (pin "2") (pinfunction "2_2") (pintype "passive"))
      (node (ref "U5") (pin "35") (pinfunction "ADC2_PA2_35") (pintype "passive"))
    )
    (net (code "63") (name "/MCU_AI03") (class "Default")
      (node (ref "U5") (pin "37") (pinfunction "ADC0_PA0_37") (pintype "passive"))
    )
    (net (code "64") (name "/MCU_AI04") (class "Default")
      (node (ref "U5") (pin "36") (pinfunction "ADC1_PA1_36") (pintype "passive"))
    )
    (net (code "65") (name "/OSC_N") (class "Default")
      (node (ref "C5") (pin "1") (pinfunction "1_1") (pintype "passive"))
      (node (ref "R31") (pin "1") (pinfunction "1_1") (pintype "passive"))
      (node (ref "U5") (pin "7") (pinfunction "XTAL2_7") (pintype "passive"))
      (node (ref "Y1") (pin "2") (pinfunction "2_2") (pintype "passive"))
    )
    (net (code "66") (name "/OSC_P") (class "Default")
      (node (ref "C4") (pin "1") (pinfunction "1_1") (pintype "passive"))
      (node (ref "R31") (pin "2") (pinfunction "0_2") (pintype "passive"))
      (node (ref "U5") (pin "8") (pinfunction "XTAL1_8") (pintype "passive"))
      (node (ref "Y1") (pin "1") (pinfunction "1_1") (pintype "passive"))
    )
    (net (code "67") (name "24V") (class "Default")
      (node (ref "D2") (pin "1") (pinfunction "A_1") (pintype "passive"))
      (node (ref "F2") (pin "2") (pinfunction "2_2") (pintype "passive"))
    )
    (net (code "68") (name "24VDI") (class "Default")
      (node (ref "D2") (pin "2") (pinfunction "K_2") (pintype "passive"))
      (node (ref "R10") (pin "1") (pinfunction "1_1") (pintype "passive"))
      (node (ref "R11") (pin "1") (pinfunction "1_1") (pintype "passive"))
      (node (ref "R12") (pin "1") (pinfunction "1_1") (pintype "passive"))
      (node (ref "R13") (pin "1") (pinfunction "1_1") (pintype "passive"))
      (node (ref "R14") (pin "1") (pinfunction "1_1") (pintype "passive"))
      (node (ref "R15") (pin "1") (pinfunction "1_1") (pintype "passive"))
      (node (ref "R16") (pin "1") (pinfunction "1_1") (pintype "passive"))
      (node (ref "R17") (pin "1") (pinfunction "1_1") (pintype "passive"))
      (node (ref "R18") (pin "1") (pinfunction "1_1") (pintype "passive"))
      (node (ref "R19") (pin "1") (pinfunction "1_1") (pintype "passive"))
      (node (ref "R20") (pin "1") (pinfunction "1_1") (pintype "passive"))
      (node (ref "R21") (pin "1") (pinfunction "1_1") (pintype "passive"))
      (node (ref "R22") (pin "1") (pinfunction "1_1") (pintype "passive"))
      (node (ref "R23") (pin "1") (pinfunction "1_1") (pintype "passive"))
      (node (ref "R24") (pin "1") (pinfunction "1_1") (pintype "passive"))
      (node (ref "R25") (pin "1") (pinfunction "1_1") (pintype "passive"))
    )
    (net (code "69") (name "CNT-12V") (class "Default")
      (node (ref "C8") (pin "2") (pinfunction "2_2") (pintype "passive"))
      (node (ref "P2") (pin "11") (pinfunction "11_11") (pintype "passive"))
      (node (ref "U4") (pin "8") (pinfunction "V_8") (pintype "passive"))
    )
    (net (code "70") (name "CNT-24V") (class "Default")
      (node (ref "F2") (pin "1") (pinfunction "1_1") (pintype "passive"))
      (node (ref "P2") (pin "8") (pinfunction "8_8") (pintype "passive"))
      (node (ref "U6") (pin "9") (pinfunction "COM_9") (pintype "passive"))
    )
    (net (code "71") (name "CNT-VCC") (class "Default")
      (node (ref "F1") (pin "1") (pinfunction "1_1") (pintype "passive"))
      (node (ref "P2") (pin "23") (pinfunction "23_23") (pintype "passive"))
    )
    (net (code "72") (name "GND") (class "Default")
      (node (ref "C1") (pin "2") (pinfunction "2_2") (pintype "passive"))
      (node (ref "C10") (pin "1") (pinfunction "1_1") (pintype "passive"))
      (node (ref "C11") (pin "2") (pinfunction "2_2") (pintype "passive"))
      (node (ref "C12") (pin "2") (pinfunction "2_2") (pintype "passive"))
      (node (ref "C13") (pin "2") (pinfunction "2_2") (pintype "passive"))
      (node (ref "C14") (pin "2") (pinfunction "2_2") (pintype "passive"))
      (node (ref "C15") (pin "2") (pinfunction "2_2") (pintype "passive"))
      (node (ref "C16") (pin "2") (pinfunction "2_2") (pintype "passive"))
      (node (ref "C17") (pin "2") (pinfunction "2_2") (pintype "passive"))
      (node (ref "C2") (pin "2") (pinfunction "2_2") (pintype "passive"))
      (node (ref "C3") (pin "2") (pinfunction "2_2") (pintype "passive"))
      (node (ref "C4") (pin "2") (pinfunction "2_2") (pintype "passive"))
      (node (ref "C5") (pin "2") (pinfunction "2_2") (pintype "passive"))
      (node (ref "C6") (pin "2") (pinfunction "2_2") (pintype "passive"))
      (node (ref "C8") (pin "1") (pinfunction "1_1") (pintype "passive"))
      (node (ref "C9") (pin "2") (pinfunction "2_2") (pintype "passive"))
      (node (ref "D1") (pin "2") (pinfunction "2_2") (pintype "passive"))
      (node (ref "D19") (pin "A") (pinfunction "A_A") (pintype "passive"))
      (node (ref "D20") (pin "A") (pinfunction "A_A") (pintype "passive"))
      (node (ref "D21") (pin "A") (pinfunction "A_A") (pintype "passive"))
      (node (ref "D22") (pin "A") (pinfunction "A_A") (pintype "passive"))
      (node (ref "P1") (pin "10") (pinfunction "10_10") (pintype "passive"))
      (node (ref "P1") (pin "4") (pinfunction "4_4") (pintype "passive"))
      (node (ref "P1") (pin "6") (pinfunction "6_6") (pintype "passive"))
      (node (ref "P1") (pin "8") (pinfunction "8_8") (pintype "passive"))
      (node (ref "P2") (pin "9") (pinfunction "9_9") (pintype "passive"))
      (node (ref "R30") (pin "1") (pinfunction "1_1") (pintype "passive"))
      (node (ref "R50") (pin "1") (pinfunction "1_1") (pintype "passive"))
      (node (ref "R51") (pin "1") (pinfunction "1_1") (pintype "passive"))
      (node (ref "R53") (pin "1") (pinfunction "1_1") (pintype "passive"))
      (node (ref "SEL1") (pin "10") (pinfunction "B1_10") (pintype "passive"))
      (node (ref "SEL1") (pin "6") (pinfunction "B5_6") (pintype "passive"))
      (node (ref "SEL1") (pin "7") (pinfunction "B4_7") (pintype "passive"))
      (node (ref "SEL1") (pin "8") (pinfunction "B3_8") (pintype "passive"))
      (node (ref "SEL1") (pin "9") (pinfunction "B2_9") (pintype "passive"))
      (node (ref "SEL2") (pin "4") (pinfunction "B3_4") (pintype "passive"))
      (node (ref "SEL2") (pin "5") (pinfunction "B2_5") (pintype "passive"))
      (node (ref "SEL2") (pin "6") (pinfunction "B1_6") (pintype "passive"))
      (node (ref "U1") (pin "11") (pinfunction "11_11") (pintype "passive"))
      (node (ref "U1") (pin "13") (pinfunction "13_13") (pintype "passive"))
      (node (ref "U1") (pin "15") (pinfunction "15_15") (pintype "passive"))
      (node (ref "U1") (pin "9") (pinfunction "9_9") (pintype "passive"))
      (node (ref "U2") (pin "11") (pinfunction "11_11") (pintype "passive"))
      (node (ref "U2") (pin "13") (pinfunction "13_13") (pintype "passive"))
      (node (ref "U2") (pin "15") (pinfunction "15_15") (pintype "passive"))
      (node (ref "U2") (pin "9") (pinfunction "9_9") (pintype "passive"))
      (node (ref "U3") (pin "7") (pinfunction "GND_7") (pintype "power_in"))
      (node (ref "U4") (pin "4") (pinfunction "G_4") (pintype "passive"))
      (node (ref "U5") (pin "18") (pinfunction "GND_18") (pintype "passive"))
      (node (ref "U5") (pin "28") (pinfunction "GND_28") (pintype "passive"))
      (node (ref "U5") (pin "39") (pinfunction "GND_39") (pintype "passive"))
      (node (ref "U5") (pin "6") (pinfunction "GND_6") (pintype "passive"))
      (node (ref "U7") (pin "5") (pinfunction "GND_5") (pintype "passive"))
    )
    (net (code "73") (name "KEY1") (class "Default")
      (node (ref "P1") (pin "1") (pinfunction "1_1") (pintype "passive"))
      (node (ref "P2") (pin "12") (pinfunction "12_12") (pintype "passive"))
      (node (ref "SEL2") (pin "3") (pinfunction "A3_3") (pintype "passive"))
      (node (ref "U5") (pin "1") (pinfunction "MOSI_PB5_1") (pintype "passive"))
    )
    (net (code "74") (name "KEY2") (class "Default")
      (node (ref "P1") (pin "9") (pinfunction "9_9") (pintype "passive"))
      (node (ref "P2") (pin "25") (pinfunction "25_25") (pintype "passive"))
      (node (ref "SEL2") (pin "2") (pinfunction "A2_2") (pintype "passive"))
      (node (ref "U5") (pin "2") (pinfunction "MISO_PB6_2") (pintype "passive"))
    )
    (net (code "75") (name "KEY3") (class "Default")
      (node (ref "P1") (pin "7") (pinfunction "7_7") (pintype "passive"))
      (node (ref "P2") (pin "24") (pinfunction "24_24") (pintype "passive"))
      (node (ref "SEL2") (pin "1") (pinfunction "A1_1") (pintype "passive"))
      (node (ref "U5") (pin "3") (pinfunction "SCK_PB7_3") (pintype "passive"))
    )
    (net (code "76") (name "Net-(C3-Pad1)") (class "Default")
      (node (ref "C3") (pin "1") (pinfunction "1_1") (pintype "passive"))
      (node (ref "R26") (pin "2") (pinfunction "2_2") (pintype "passive"))
      (node (ref "R29") (pin "1") (pinfunction "1_1") (pintype "passive"))
    )
    (net (code "77") (name "Net-(D1-Pad1)") (class "Default")
      (node (ref "D1") (pin "1") (pinfunction "1_1") (pintype "passive"))
      (node (ref "R9") (pin "1") (pinfunction "1_1") (pintype "passive"))
    )
    (net (code "78") (name "Net-(F5-Pad1)") (class "Default")
      (node (ref "F5") (pin "1") (pinfunction "1_1") (pintype "passive"))
      (node (ref "R48") (pin "1") (pinfunction "1_1") (pintype "passive"))
    )
    (net (code "79") (name "Net-(F6-Pad1)") (class "Default")
      (node (ref "F6") (pin "1") (pinfunction "1_1") (pintype "passive"))
      (node (ref "R49") (pin "1") (pinfunction "1_1") (pintype "passive"))
    )
    (net (code "80") (name "Net-(Q1-B)") (class "Default")
      (node (ref "Q1") (pin "2") (pinfunction "B_2") (pintype "passive"))
      (node (ref "R42") (pin "1") (pintype "passive"))
    )
    (net (code "81") (name "Net-(Q2-B)") (class "Default")
      (node (ref "Q2") (pin "2") (pinfunction "B_2") (pintype "passive"))
      (node (ref "R46") (pin "1") (pintype "passive"))
    )
    (net (code "82") (name "Net-(R10-Pad2)") (class "Default")
      (node (ref "R10") (pin "2") (pinfunction "2_2") (pintype "passive"))
      (node (ref "U1") (pin "1") (pinfunction "1_1") (pintype "passive"))
    )
    (net (code "83") (name "Net-(R12-Pad2)") (class "Default")
      (node (ref "R12") (pin "2") (pinfunction "2_2") (pintype "passive"))
      (node (ref "U1") (pin "3") (pinfunction "3_3") (pintype "passive"))
    )
    (net (code "84") (name "Net-(R14-Pad2)") (class "Default")
      (node (ref "R14") (pin "2") (pinfunction "2_2") (pintype "passive"))
      (node (ref "U1") (pin "5") (pinfunction "5_5") (pintype "passive"))
    )
    (net (code "85") (name "Net-(R16-Pad2)") (class "Default")
      (node (ref "R16") (pin "2") (pinfunction "2_2") (pintype "passive"))
      (node (ref "U1") (pin "7") (pinfunction "7_7") (pintype "passive"))
    )
    (net (code "86") (name "Net-(R18-Pad2)") (class "Default")
      (node (ref "R18") (pin "2") (pinfunction "2_2") (pintype "passive"))
      (node (ref "U2") (pin "1") (pinfunction "1_1") (pintype "passive"))
    )
    (net (code "87") (name "Net-(R20-Pad2)") (class "Default")
      (node (ref "R20") (pin "2") (pinfunction "2_2") (pintype "passive"))
      (node (ref "U2") (pin "3") (pinfunction "3_3") (pintype "passive"))
    )
    (net (code "88") (name "Net-(R22-Pad2)") (class "Default")
      (node (ref "R22") (pin "2") (pinfunction "2_2") (pintype "passive"))
      (node (ref "U2") (pin "5") (pinfunction "5_5") (pintype "passive"))
    )
    (net (code "89") (name "Net-(R24-Pad2)") (class "Default")
      (node (ref "R24") (pin "2") (pinfunction "2_2") (pintype "passive"))
      (node (ref "U2") (pin "7") (pinfunction "7_7") (pintype "passive"))
    )
    (net (code "90") (name "Net-(U3-A)") (class "Default")
      (node (ref "R27") (pin "1") (pinfunction "1_1") (pintype "passive"))
      (node (ref "U3") (pin "1") (pinfunction "A_1") (pintype "passive"))
      (node (ref "U3") (pin "2") (pinfunction "B_2") (pintype "passive"))
    )
    (net (code "91") (name "Net-(U3-CLK)") (class "Default")
      (node (ref "R28") (pin "1") (pinfunction "1_1") (pintype "passive"))
      (node (ref "U3") (pin "8") (pinfunction "CLK_8") (pintype "passive"))
    )
    (net (code "92") (name "Net-(U3-QA)") (class "Default")
      (node (ref "R34") (pin "1") (pinfunction "1_1") (pintype "passive"))
      (node (ref "U3") (pin "3") (pinfunction "QA_3") (pintype "passive"))
    )
    (net (code "93") (name "Net-(U3-QB)") (class "Default")
      (node (ref "R35") (pin "1") (pinfunction "1_1") (pintype "passive"))
      (node (ref "U3") (pin "4") (pinfunction "QB_4") (pintype "passive"))
    )
    (net (code "94") (name "Net-(U3-QC)") (class "Default")
      (node (ref "R36") (pin "1") (pinfunction "1_1") (pintype "passive"))
      (node (ref "U3") (pin "5") (pinfunction "QC_5") (pintype "passive"))
    )
    (net (code "95") (name "Net-(U3-QD)") (class "Default")
      (node (ref "R37") (pin "1") (pinfunction "1_1") (pintype "passive"))
      (node (ref "U3") (pin "6") (pinfunction "QD_6") (pintype "passive"))
    )
    (net (code "96") (name "Net-(U3-QE)") (class "Default")
      (node (ref "R38") (pin "1") (pinfunction "1_1") (pintype "passive"))
      (node (ref "U3") (pin "10") (pinfunction "QE_10") (pintype "passive"))
    )
    (net (code "97") (name "Net-(U3-QF)") (class "Default")
      (node (ref "R39") (pin "1") (pinfunction "1_1") (pintype "passive"))
      (node (ref "U3") (pin "11") (pinfunction "QF_11") (pintype "passive"))
    )
    (net (code "98") (name "Net-(U3-QG)") (class "Default")
      (node (ref "R40") (pin "1") (pinfunction "1_1") (pintype "passive"))
      (node (ref "U3") (pin "12") (pinfunction "QG_12") (pintype "passive"))
    )
    (net (code "99") (name "Net-(U3-QH)") (class "Default")
      (node (ref "R41") (pin "1") (pinfunction "1_1") (pintype "passive"))
      (node (ref "U3") (pin "13") (pinfunction "QH_13") (pintype "passive"))
    )
    (net (code "100") (name "Net-(U4A-+)") (class "Default")
      (node (ref "C6") (pin "1") (pinfunction "1_1") (pintype "passive"))
      (node (ref "R29") (pin "2") (pinfunction "2_2") (pintype "passive"))
      (node (ref "U4") (pin "3") (pinfunction "+_3") (pintype "passive"))
    )
    (net (code "101") (name "Net-(U4A---)") (class "Default")
      (node (ref "C7") (pin "1") (pinfunction "1_1") (pintype "passive"))
      (node (ref "R30") (pin "2") (pinfunction "2_2") (pintype "passive"))
      (node (ref "R32") (pin "1") (pinfunction "1_1") (pintype "passive"))
      (node (ref "U4") (pin "2") (pinfunction "--_2") (pintype "passive"))
    )
    (net (code "102") (name "Net-(U4A-OUT)") (class "Default")
      (node (ref "R43") (pin "1") (pinfunction "1_1") (pintype "passive"))
      (node (ref "U4") (pin "1") (pinfunction "OUT_1") (pintype "passive"))
    )
    (net (code "103") (name "Net-(U4B-+)") (class "Default")
      (node (ref "C7") (pin "2") (pinfunction "2_2") (pintype "passive"))
      (node (ref "C9") (pin "1") (pinfunction "1_1") (pintype "passive"))
      (node (ref "R32") (pin "2") (pinfunction "2_2") (pintype "passive"))
      (node (ref "R43") (pin "2") (pinfunction "2_2") (pintype "passive"))
      (node (ref "U4") (pin "5") (pinfunction "+_5") (pintype "passive"))
    )
    (net (code "104") (name "Net-(U4B---)") (class "Default")
      (node (ref "R54") (pin "2") (pinfunction "2_2") (pintype "passive"))
      (node (ref "U4") (pin "6") (pinfunction "--_6") (pintype "passive"))
      (node (ref "U4") (pin "7") (pinfunction "OUT_7") (pintype "passive"))
    )
    (net (code "105") (name "Net-(U5-AREF)") (class "Default")
      (node (ref "C14") (pin "1") (pinfunction "1_1") (pintype "passive"))
      (node (ref "U5") (pin "29") (pinfunction "AREF_29") (pintype "passive"))
    )
    (net (code "106") (name "Net-(U7-A)") (class "Default")
      (node (ref "D22") (pin "K") (pinfunction "K_K") (pintype "passive"))
      (node (ref "F4") (pin "2") (pinfunction "2_2") (pintype "passive"))
      (node (ref "R47") (pin "2") (pinfunction "2_2") (pintype "passive"))
      (node (ref "R52") (pin "2") (pinfunction "2_2") (pintype "passive"))
      (node (ref "U7") (pin "6") (pinfunction "A_6") (pintype "passive"))
    )
    (net (code "107") (name "Net-(U7-B)") (class "Default")
      (node (ref "D19") (pin "K") (pinfunction "K_K") (pintype "passive"))
      (node (ref "F3") (pin "2") (pinfunction "2_2") (pintype "passive"))
      (node (ref "R52") (pin "1") (pinfunction "1_1") (pintype "passive"))
      (node (ref "R53") (pin "2") (pinfunction "2_2") (pintype "passive"))
      (node (ref "U7") (pin "7") (pinfunction "B_7") (pintype "passive"))
    )
    (net (code "108") (name "RESET") (class "Default")
      (node (ref "P1") (pin "5") (pinfunction "5_5") (pintype "passive"))
      (node (ref "R44") (pin "1") (pinfunction "1_1") (pintype "passive"))
      (node (ref "U5") (pin "4") (pinfunction "RESET_4") (pintype "passive"))
    )
    (net (code "109") (name "VCC") (class "Default")
      (node (ref "C1") (pin "1") (pinfunction "1_1") (pintype "passive"))
      (node (ref "C10") (pin "2") (pinfunction "2_2") (pintype "passive"))
      (node (ref "C11") (pin "1") (pinfunction "1_1") (pintype "passive"))
      (node (ref "C12") (pin "1") (pinfunction "1_1") (pintype "passive"))
      (node (ref "C13") (pin "1") (pinfunction "1_1") (pintype "passive"))
      (node (ref "C15") (pin "1") (pinfunction "1_1") (pintype "passive"))
      (node (ref "C2") (pin "1") (pinfunction "1_1") (pintype "passive"))
      (node (ref "F1") (pin "2") (pinfunction "2_2") (pintype "passive"))
      (node (ref "P1") (pin "2") (pinfunction "2_2") (pintype "passive"))
      (node (ref "Q1") (pin "3") (pinfunction "E_3") (pintype "passive"))
      (node (ref "Q2") (pin "3") (pinfunction "E_3") (pintype "passive"))
      (node (ref "R1") (pin "2") (pinfunction "2_2") (pintype "passive"))
      (node (ref "R2") (pin "2") (pinfunction "2_2") (pintype "passive"))
      (node (ref "R3") (pin "2") (pinfunction "2_2") (pintype "passive"))
      (node (ref "R33") (pin "1") (pintype "passive"))
      (node (ref "R4") (pin "2") (pinfunction "2_2") (pintype "passive"))
      (node (ref "R44") (pin "2") (pinfunction "0_2") (pintype "passive"))
      (node (ref "R45") (pin "1") (pintype "passive"))
      (node (ref "R47") (pin "1") (pinfunction "1_1") (pintype "passive"))
      (node (ref "R5") (pin "2") (pinfunction "2_2") (pintype "passive"))
      (node (ref "R6") (pin "2") (pinfunction "2_2") (pintype "passive"))
      (node (ref "R7") (pin "2") (pinfunction "2_2") (pintype "passive"))
      (node (ref "R8") (pin "2") (pinfunction "2_2") (pintype "passive"))
      (node (ref "R9") (pin "2") (pinfunction "2_2") (pintype "passive"))
      (node (ref "U3") (pin "14") (pinfunction "VCC_14") (pintype "power_in"))
      (node (ref "U3") (pin "9") (pinfunction "CLR_9") (pintype "passive"))
      (node (ref "U5") (pin "17") (pinfunction "VCC_17") (pintype "passive"))
      (node (ref "U5") (pin "27") (pinfunction "AVCC_27") (pintype "passive"))
      (node (ref "U5") (pin "38") (pinfunction "VCC_38") (pintype "passive"))
      (node (ref "U5") (pin "5") (pinfunction "VCC_5") (pintype "passive"))
      (node (ref "U7") (pin "8") (pinfunction "VCC_8") (pintype "passive"))
    )
    (net (code "110") (name "unconnected-(P1-Pad3)") (class "Default")
      (node (ref "P1") (pin "3") (pinfunction "3_3") (pintype "passive"))
    )
    (net (code "111") (name "unconnected-(U6-IN1-Pad1)") (class "Default")
      (node (ref "U6") (pin "1") (pinfunction "IN1_1") (pintype "input"))
    )
    (net (code "112") (name "unconnected-(U6-IN2-Pad2)") (class "Default")
      (node (ref "U6") (pin "2") (pinfunction "IN2_2") (pintype "input"))
    )
    (net (code "113") (name "unconnected-(U6-IN3-Pad3)") (class "Default")
      (node (ref "U6") (pin "3") (pinfunction "IN3_3") (pintype "input"))
    )
    (net (code "114") (name "unconnected-(U6-OUT1-Pad16)") (class "Default")
      (node (ref "U6") (pin "16") (pinfunction "OUT1_16") (pintype "open_collector"))
    )
    (net (code "115") (name "unconnected-(U6-OUT2-Pad15)") (class "Default")
      (node (ref "U6") (pin "15") (pinfunction "OUT2_15") (pintype "open_collector"))
    )
    (net (code "116") (name "unconnected-(U6-OUT3-Pad14)") (class "Default")
      (node (ref "U6") (pin "14") (pinfunction "OUT3_14") (pintype "open_collector"))
    )
  )
)
